# Bank0-13-33.net
KiCad netlist of a schematic drawn in Altium Designer
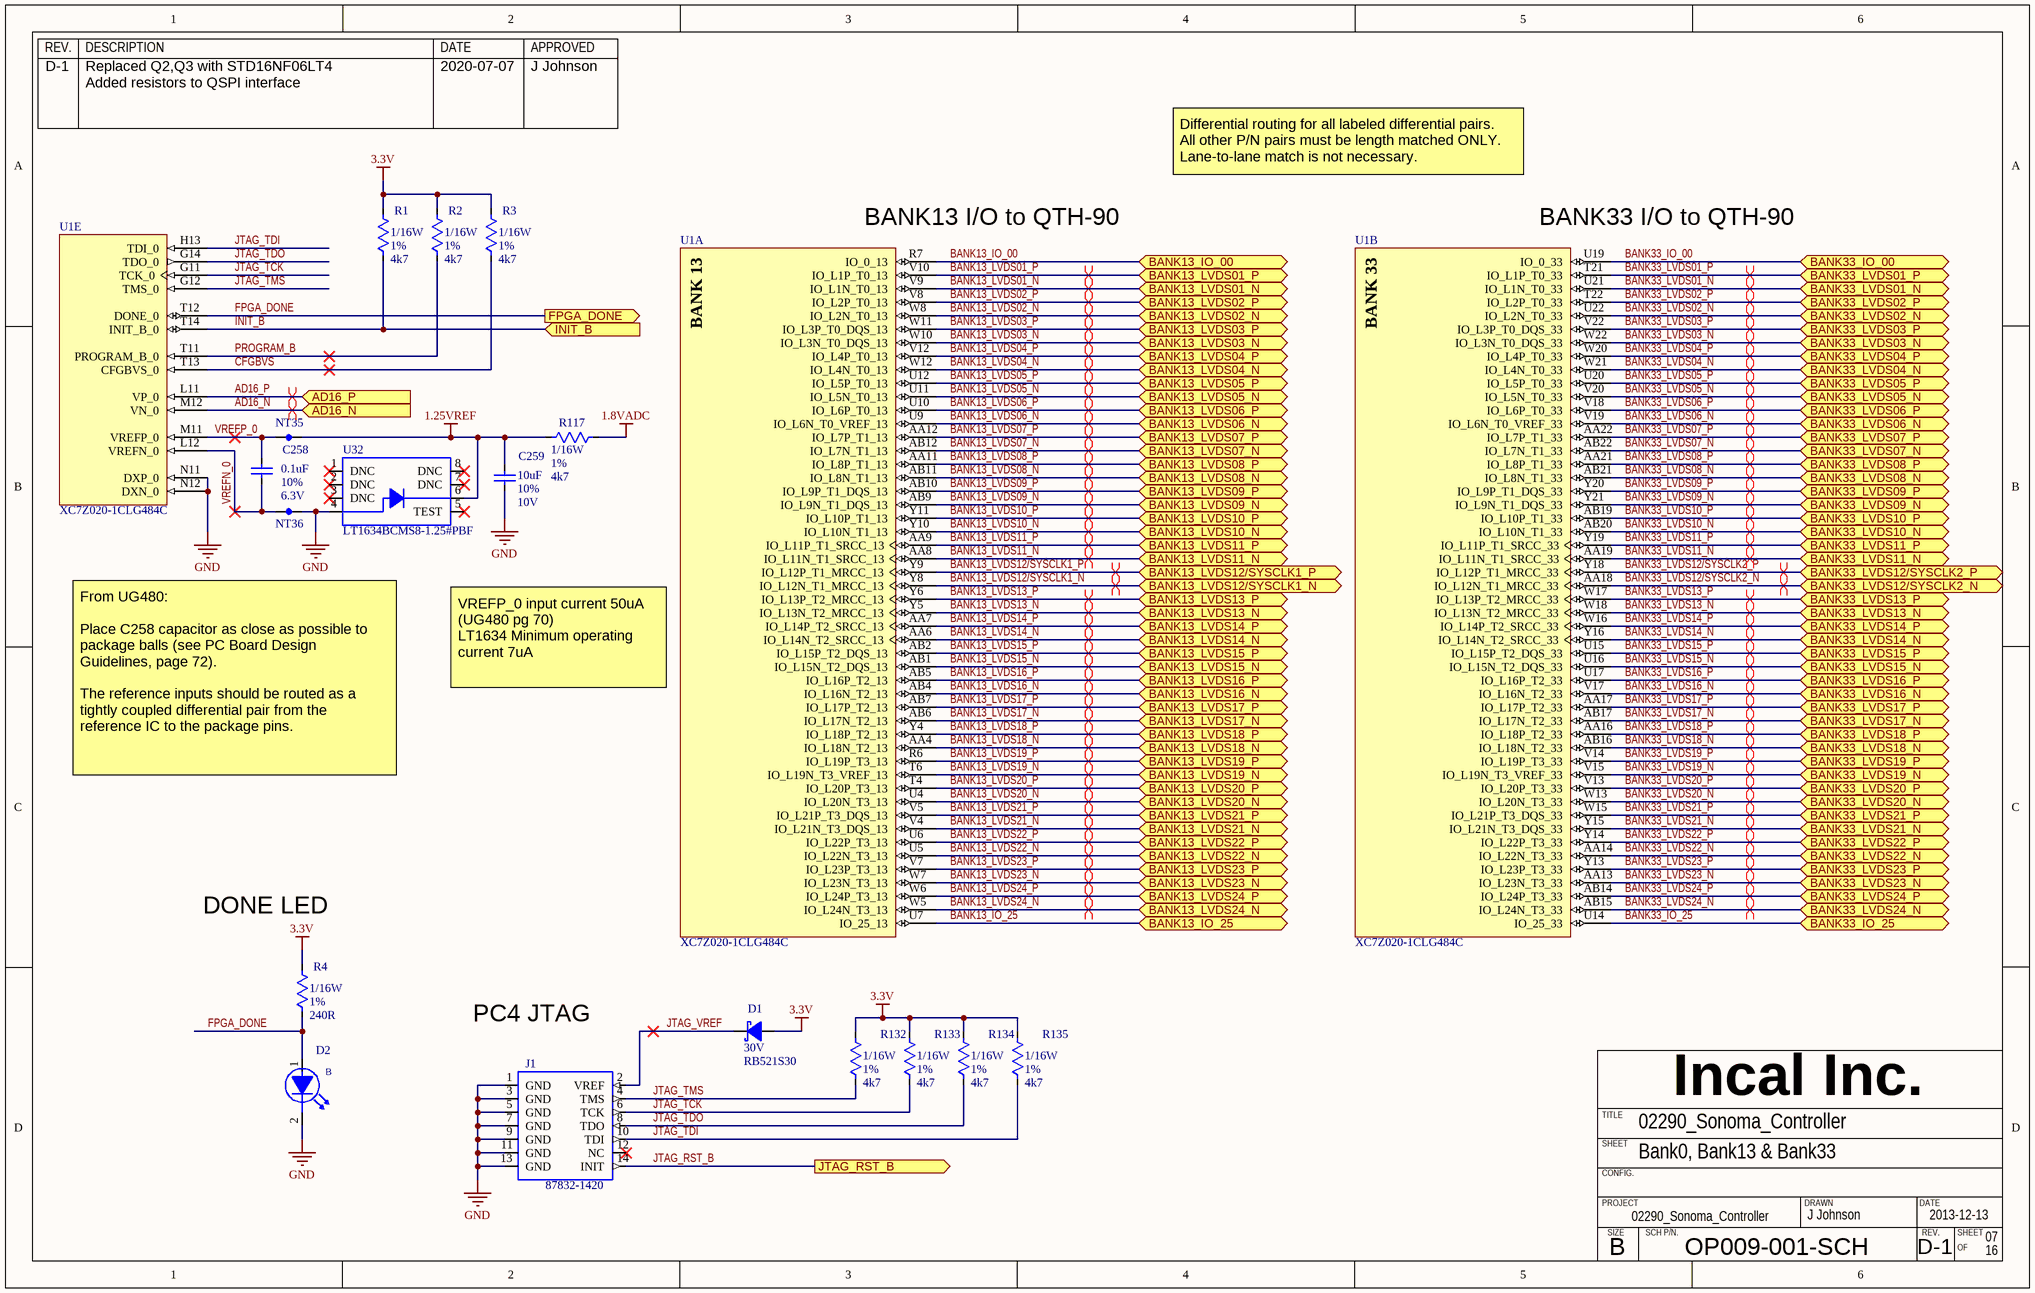
[diagram p0: Bank0-13-33.SchDoc]

(export (version "E")
  (design (tool "Eeschema 10.0.6"))
  (components
    (comp (ref "C258")
      (value "0.1uF")
      (footprint "CAPC0603X33N")
      (description "Capacitor ceramic, X5R, 0.1uF, 6.3V, 10%, -55 to +125 C, EIA0201")
      (fields
        (field (name "TOLERANCE") "10%")
        (field (name "VOLTAGE") "6.3V")
        (field (name "Comment") "CAPACITOR_NP_TYPE1")
      )
      (libsource (lib "parts") (part "CAPACITOR_NP_TYPE1"))
    )
    (comp (ref "C259")
      (value "10uF")
      (footprint "CAPC1608X38N")
      (description "Capacitor ceramic, X5R, 10uF, 10V, 10%, -55 to +85 C, EIA0603")
      (fields
        (field (name "TOLERANCE") "10%")
        (field (name "VOLTAGE") "10V")
        (field (name "Comment") "CAPACITOR_NP_TYPE1")
      )
      (libsource (lib "parts") (part "CAPACITOR_NP_TYPE1"))
    )
    (comp (ref "D1")
      (value "RB521S30")
      (footprint "SOD15080X70")
      (description "Diode schottky, 30V, 200mA, SOD-523F")
      (fields (field (name "VOLTAGE") "30V") (field (name "Comment") "DIODE_SCHOTTKY_TYPE1"))
      (libsource (lib "parts") (part "DIODE_SCHOTTKY_TYPE1"))
    )
    (comp (ref "D2")
      (value "LED_BLU")
      (footprint "LEDM1608X38N-BLU")
      (description "Led, Blue, 150mcd, SMT, LTST-C191TBKT, -20 to +80 C, 0603")
      (fields (field (name "POWER") "120mW") (field (name "VOLTAGE") "3.2V"))
      (libsource (lib "parts") (part "LED_BLU"))
    )
    (comp (ref "J1")
      (value "XILINX-JTAG-2x7")
      (footprint "87832-1420")
      (description "Connector Header 2mm, 2x7, SMT, Keyed, Shrouded, 0V, 0A, -55 to +105 C")
      (fields
        (field (name "POWER") "Pow")
        (field (name "VOLTAGE") "0V")
        (field (name "MFG PART NUMBER 1") "87832-1420")
      )
      (libsource (lib "parts") (part "XILINX-JTAG-2x7"))
    )
    (comp (ref "NT35")
      (value "NET_TIE_1X1")
      (footprint "NET_TIE_1X1")
      (description "Net Tie 1 to 1")
      (libsource (lib "parts") (part "NET_TIE_1X1"))
    )
    (comp (ref "NT36")
      (value "NET_TIE_1X1")
      (footprint "NET_TIE_1X1")
      (description "Net Tie 1 to 1")
      (libsource (lib "parts") (part "NET_TIE_1X1"))
    )
    (comp (ref "R1")
      (value "4k7")
      (footprint "RESC1005X33N")
      (description "Resistor, 4k7, 1/16W, 1%, -55 to +155 C, EIA0402")
      (fields (field (name "VOLTAGE") "50V") (field (name "POWER") "1/16W") (field (name "TOLERANCE") "1%"))
      (libsource (lib "parts") (part "RESISTOR_TYPE1"))
    )
    (comp (ref "R2")
      (value "4k7")
      (footprint "RESC1005X33N")
      (description "Resistor, 4k7, 1/16W, 1%, -55 to +155 C, EIA0402")
      (fields (field (name "VOLTAGE") "50V") (field (name "POWER") "1/16W") (field (name "TOLERANCE") "1%"))
      (libsource (lib "parts") (part "RESISTOR_TYPE1"))
    )
    (comp (ref "R3")
      (value "4k7")
      (footprint "RESC1005X33N")
      (description "Resistor, 4k7, 1/16W, 1%, -55 to +155 C, EIA0402")
      (fields (field (name "VOLTAGE") "50V") (field (name "POWER") "1/16W") (field (name "TOLERANCE") "1%"))
      (libsource (lib "parts") (part "RESISTOR_TYPE1"))
    )
    (comp (ref "R4")
      (value "240R")
      (footprint "RESC1005X33N")
      (description "Resistor, 240R, 1/16W, 1%, -50 to +155 C, EIA0402, EIA(M)1005")
      (fields (field (name "VOLTAGE") "50V") (field (name "POWER") "1/16W") (field (name "TOLERANCE") "1%"))
      (libsource (lib "parts") (part "RESISTOR_TYPE1"))
    )
    (comp (ref "R117")
      (value "4k7")
      (footprint "RESC1005X33N")
      (description "Resistor, 4k7, 1/16W, 1%, -55 to +155 C, EIA0402")
      (fields (field (name "VOLTAGE") "50V") (field (name "POWER") "1/16W") (field (name "TOLERANCE") "1%"))
      (libsource (lib "parts") (part "RESISTOR_TYPE1"))
    )
    (comp (ref "R132")
      (value "4k7")
      (footprint "RESC1005X33N")
      (description "Resistor, 4k7, 1/16W, 1%, -55 to +155 C, EIA0402")
      (fields (field (name "VOLTAGE") "50V") (field (name "POWER") "1/16W") (field (name "TOLERANCE") "1%"))
      (libsource (lib "parts") (part "RESISTOR_TYPE1"))
    )
    (comp (ref "R133")
      (value "4k7")
      (footprint "RESC1005X33N")
      (description "Resistor, 4k7, 1/16W, 1%, -55 to +155 C, EIA0402")
      (fields (field (name "VOLTAGE") "50V") (field (name "POWER") "1/16W") (field (name "TOLERANCE") "1%"))
      (libsource (lib "parts") (part "RESISTOR_TYPE1"))
    )
    (comp (ref "R134")
      (value "4k7")
      (footprint "RESC1005X33N")
      (description "Resistor, 4k7, 1/16W, 1%, -55 to +155 C, EIA0402")
      (fields (field (name "VOLTAGE") "50V") (field (name "POWER") "1/16W") (field (name "TOLERANCE") "1%"))
      (libsource (lib "parts") (part "RESISTOR_TYPE1"))
    )
    (comp (ref "R135")
      (value "4k7")
      (footprint "RESC1005X33N")
      (description "Resistor, 4k7, 1/16W, 1%, -55 to +155 C, EIA0402")
      (fields (field (name "VOLTAGE") "50V") (field (name "POWER") "1/16W") (field (name "TOLERANCE") "1%"))
      (libsource (lib "parts") (part "RESISTOR_TYPE1"))
    )
    (comp (ref "U1")
      (value "XC7Z020-1CLG484C")
      (footprint "CLG484")
      (description "667 MHz Zynq™-7000 AP SoC, 130 PS I/O, 200 FPGA I/O, 484-Ball BGA, Speed Grade 1, Commercial Grade")
      (fields (field (name "GENERIC PART NUMBER") "XC7Z020") (field (name "MANUFACTURER") "Xilinx"))
      (libsource (lib "") (part "XC7Z020-1CLG484C_1"))
    )
    (comp (ref "U32")
      (value "LT1634")
      (footprint "SOP65P490X110-8N")
      (description "Reference Shunt 1.25V, 10ppm, 0.05%")
      (fields
        (field (name "POWER") "Pow")
        (field (name "TOLERANCE") "±0.05%")
        (field (name "MFG PART NUMBER 1") "LT1634BCMS8-1.25#PBF")
      )
      (libsource (lib "parts") (part "LT1634"))
    )
  )
  (nets
    (net (code "1") (name "/AD16_N") (class "Default")
      (node (ref "U1") (pin "M12") (pinfunction "VN_0_M12") (pintype "input"))
    )
    (net (code "2") (name "/AD16_P") (class "Default")
      (node (ref "U1") (pin "L11") (pinfunction "VP_0_L11") (pintype "input"))
    )
    (net (code "3") (name "/BANK13_IO_00") (class "Default")
      (node (ref "U1") (pin "R7") (pinfunction "IO_0_13_R7") (pintype "bidirectional"))
    )
    (net (code "4") (name "/BANK13_IO_25") (class "Default")
      (node (ref "U1") (pin "U7") (pinfunction "IO_25_13_U7") (pintype "bidirectional"))
    )
    (net (code "5") (name "/BANK13_LVDS01_N") (class "Default")
      (node (ref "U1") (pin "V9") (pinfunction "IO_L1N_T0_13_V9") (pintype "bidirectional"))
    )
    (net (code "6") (name "/BANK13_LVDS01_P") (class "Default")
      (node (ref "U1") (pin "V10") (pinfunction "IO_L1P_T0_13_V10") (pintype "bidirectional"))
    )
    (net (code "7") (name "/BANK13_LVDS02_N") (class "Default")
      (node (ref "U1") (pin "W8") (pinfunction "IO_L2N_T0_13_W8") (pintype "bidirectional"))
    )
    (net (code "8") (name "/BANK13_LVDS02_P") (class "Default")
      (node (ref "U1") (pin "V8") (pinfunction "IO_L2P_T0_13_V8") (pintype "bidirectional"))
    )
    (net (code "9") (name "/BANK13_LVDS03_N") (class "Default")
      (node (ref "U1") (pin "W10") (pinfunction "IO_L3N_T0_DQS_13_W10") (pintype "bidirectional"))
    )
    (net (code "10") (name "/BANK13_LVDS03_P") (class "Default")
      (node (ref "U1") (pin "W11") (pinfunction "IO_L3P_T0_DQS_13_W11") (pintype "bidirectional"))
    )
    (net (code "11") (name "/BANK13_LVDS04_N") (class "Default")
      (node (ref "U1") (pin "W12") (pinfunction "IO_L4N_T0_13_W12") (pintype "bidirectional"))
    )
    (net (code "12") (name "/BANK13_LVDS04_P") (class "Default")
      (node (ref "U1") (pin "V12") (pinfunction "IO_L4P_T0_13_V12") (pintype "bidirectional"))
    )
    (net (code "13") (name "/BANK13_LVDS05_N") (class "Default")
      (node (ref "U1") (pin "U11") (pinfunction "IO_L5N_T0_13_U11") (pintype "bidirectional"))
    )
    (net (code "14") (name "/BANK13_LVDS05_P") (class "Default")
      (node (ref "U1") (pin "U12") (pinfunction "IO_L5P_T0_13_U12") (pintype "bidirectional"))
    )
    (net (code "15") (name "/BANK13_LVDS06_N") (class "Default")
      (node (ref "U1") (pin "U9") (pinfunction "IO_L6N_T0_VREF_13_U9") (pintype "bidirectional"))
    )
    (net (code "16") (name "/BANK13_LVDS06_P") (class "Default")
      (node (ref "U1") (pin "U10") (pinfunction "IO_L6P_T0_13_U10") (pintype "bidirectional"))
    )
    (net (code "17") (name "/BANK13_LVDS07_N") (class "Default")
      (node (ref "U1") (pin "AB12") (pinfunction "IO_L7N_T1_13_AB12") (pintype "bidirectional"))
    )
    (net (code "18") (name "/BANK13_LVDS07_P") (class "Default")
      (node (ref "U1") (pin "AA12") (pinfunction "IO_L7P_T1_13_AA12") (pintype "bidirectional"))
    )
    (net (code "19") (name "/BANK13_LVDS08_N") (class "Default")
      (node (ref "U1") (pin "AB11") (pinfunction "IO_L8N_T1_13_AB11") (pintype "bidirectional"))
    )
    (net (code "20") (name "/BANK13_LVDS08_P") (class "Default")
      (node (ref "U1") (pin "AA11") (pinfunction "IO_L8P_T1_13_AA11") (pintype "bidirectional"))
    )
    (net (code "21") (name "/BANK13_LVDS09_N") (class "Default")
      (node (ref "U1") (pin "AB9") (pinfunction "IO_L9N_T1_DQS_13_AB9") (pintype "bidirectional"))
    )
    (net (code "22") (name "/BANK13_LVDS09_P") (class "Default")
      (node (ref "U1") (pin "AB10") (pinfunction "IO_L9P_T1_DQS_13_AB10") (pintype "bidirectional"))
    )
    (net (code "23") (name "/BANK13_LVDS10_N") (class "Default")
      (node (ref "U1") (pin "Y10") (pinfunction "IO_L10N_T1_13_Y10") (pintype "bidirectional"))
    )
    (net (code "24") (name "/BANK13_LVDS10_P") (class "Default")
      (node (ref "U1") (pin "Y11") (pinfunction "IO_L10P_T1_13_Y11") (pintype "bidirectional"))
    )
    (net (code "25") (name "/BANK13_LVDS11_N") (class "Default")
      (node (ref "U1") (pin "AA8") (pinfunction "IO_L11N_T1_SRCC_13_AA8") (pintype "bidirectional"))
    )
    (net (code "26") (name "/BANK13_LVDS11_P") (class "Default")
      (node (ref "U1") (pin "AA9") (pinfunction "IO_L11P_T1_SRCC_13_AA9") (pintype "bidirectional"))
    )
    (net (code "27") (name "/BANK13_LVDS12{slash}SYSCLK1_N") (class "Default")
      (node (ref "U1") (pin "Y8") (pinfunction "IO_L12N_T1_MRCC_13_Y8") (pintype "bidirectional"))
    )
    (net (code "28") (name "/BANK13_LVDS12{slash}SYSCLK1_P") (class "Default")
      (node (ref "U1") (pin "Y9") (pinfunction "IO_L12P_T1_MRCC_13_Y9") (pintype "bidirectional"))
    )
    (net (code "29") (name "/BANK13_LVDS13_N") (class "Default")
      (node (ref "U1") (pin "Y5") (pinfunction "IO_L13N_T2_MRCC_13_Y5") (pintype "bidirectional"))
    )
    (net (code "30") (name "/BANK13_LVDS13_P") (class "Default")
      (node (ref "U1") (pin "Y6") (pinfunction "IO_L13P_T2_MRCC_13_Y6") (pintype "bidirectional"))
    )
    (net (code "31") (name "/BANK13_LVDS14_N") (class "Default")
      (node (ref "U1") (pin "AA6") (pinfunction "IO_L14N_T2_SRCC_13_AA6") (pintype "bidirectional"))
    )
    (net (code "32") (name "/BANK13_LVDS14_P") (class "Default")
      (node (ref "U1") (pin "AA7") (pinfunction "IO_L14P_T2_SRCC_13_AA7") (pintype "bidirectional"))
    )
    (net (code "33") (name "/BANK13_LVDS15_N") (class "Default")
      (node (ref "U1") (pin "AB1") (pinfunction "IO_L15N_T2_DQS_13_AB1") (pintype "bidirectional"))
    )
    (net (code "34") (name "/BANK13_LVDS15_P") (class "Default")
      (node (ref "U1") (pin "AB2") (pinfunction "IO_L15P_T2_DQS_13_AB2") (pintype "bidirectional"))
    )
    (net (code "35") (name "/BANK13_LVDS16_N") (class "Default")
      (node (ref "U1") (pin "AB4") (pinfunction "IO_L16N_T2_13_AB4") (pintype "bidirectional"))
    )
    (net (code "36") (name "/BANK13_LVDS16_P") (class "Default")
      (node (ref "U1") (pin "AB5") (pinfunction "IO_L16P_T2_13_AB5") (pintype "bidirectional"))
    )
    (net (code "37") (name "/BANK13_LVDS17_N") (class "Default")
      (node (ref "U1") (pin "AB6") (pinfunction "IO_L17N_T2_13_AB6") (pintype "bidirectional"))
    )
    (net (code "38") (name "/BANK13_LVDS17_P") (class "Default")
      (node (ref "U1") (pin "AB7") (pinfunction "IO_L17P_T2_13_AB7") (pintype "bidirectional"))
    )
    (net (code "39") (name "/BANK13_LVDS18_N") (class "Default")
      (node (ref "U1") (pin "AA4") (pinfunction "IO_L18N_T2_13_AA4") (pintype "bidirectional"))
    )
    (net (code "40") (name "/BANK13_LVDS18_P") (class "Default")
      (node (ref "U1") (pin "Y4") (pinfunction "IO_L18P_T2_13_Y4") (pintype "bidirectional"))
    )
    (net (code "41") (name "/BANK13_LVDS19_N") (class "Default")
      (node (ref "U1") (pin "T6") (pinfunction "IO_L19N_T3_VREF_13_T6") (pintype "bidirectional"))
    )
    (net (code "42") (name "/BANK13_LVDS19_P") (class "Default")
      (node (ref "U1") (pin "R6") (pinfunction "IO_L19P_T3_13_R6") (pintype "bidirectional"))
    )
    (net (code "43") (name "/BANK13_LVDS20_N") (class "Default")
      (node (ref "U1") (pin "U4") (pinfunction "IO_L20N_T3_13_U4") (pintype "bidirectional"))
    )
    (net (code "44") (name "/BANK13_LVDS20_P") (class "Default")
      (node (ref "U1") (pin "T4") (pinfunction "IO_L20P_T3_13_T4") (pintype "bidirectional"))
    )
    (net (code "45") (name "/BANK13_LVDS21_N") (class "Default")
      (node (ref "U1") (pin "V4") (pinfunction "IO_L21N_T3_DQS_13_V4") (pintype "bidirectional"))
    )
    (net (code "46") (name "/BANK13_LVDS21_P") (class "Default")
      (node (ref "U1") (pin "V5") (pinfunction "IO_L21P_T3_DQS_13_V5") (pintype "bidirectional"))
    )
    (net (code "47") (name "/BANK13_LVDS22_N") (class "Default")
      (node (ref "U1") (pin "U5") (pinfunction "IO_L22N_T3_13_U5") (pintype "bidirectional"))
    )
    (net (code "48") (name "/BANK13_LVDS22_P") (class "Default")
      (node (ref "U1") (pin "U6") (pinfunction "IO_L22P_T3_13_U6") (pintype "bidirectional"))
    )
    (net (code "49") (name "/BANK13_LVDS23_N") (class "Default")
      (node (ref "U1") (pin "W7") (pinfunction "IO_L23N_T3_13_W7") (pintype "bidirectional"))
    )
    (net (code "50") (name "/BANK13_LVDS23_P") (class "Default")
      (node (ref "U1") (pin "V7") (pinfunction "IO_L23P_T3_13_V7") (pintype "bidirectional"))
    )
    (net (code "51") (name "/BANK13_LVDS24_N") (class "Default")
      (node (ref "U1") (pin "W5") (pinfunction "IO_L24N_T3_13_W5") (pintype "bidirectional"))
    )
    (net (code "52") (name "/BANK13_LVDS24_P") (class "Default")
      (node (ref "U1") (pin "W6") (pinfunction "IO_L24P_T3_13_W6") (pintype "bidirectional"))
    )
    (net (code "53") (name "/BANK33_IO_00") (class "Default")
      (node (ref "U1") (pin "U19") (pinfunction "IO_0_33_U19") (pintype "bidirectional"))
    )
    (net (code "54") (name "/BANK33_IO_25") (class "Default")
      (node (ref "U1") (pin "U14") (pinfunction "IO_25_33_U14") (pintype "bidirectional"))
    )
    (net (code "55") (name "/BANK33_LVDS01_N") (class "Default")
      (node (ref "U1") (pin "U21") (pinfunction "IO_L1N_T0_33_U21") (pintype "bidirectional"))
    )
    (net (code "56") (name "/BANK33_LVDS01_P") (class "Default")
      (node (ref "U1") (pin "T21") (pinfunction "IO_L1P_T0_33_T21") (pintype "bidirectional"))
    )
    (net (code "57") (name "/BANK33_LVDS02_N") (class "Default")
      (node (ref "U1") (pin "U22") (pinfunction "IO_L2N_T0_33_U22") (pintype "bidirectional"))
    )
    (net (code "58") (name "/BANK33_LVDS02_P") (class "Default")
      (node (ref "U1") (pin "T22") (pinfunction "IO_L2P_T0_33_T22") (pintype "bidirectional"))
    )
    (net (code "59") (name "/BANK33_LVDS03_N") (class "Default")
      (node (ref "U1") (pin "W22") (pinfunction "IO_L3N_T0_DQS_33_W22") (pintype "bidirectional"))
    )
    (net (code "60") (name "/BANK33_LVDS03_P") (class "Default")
      (node (ref "U1") (pin "V22") (pinfunction "IO_L3P_T0_DQS_33_V22") (pintype "bidirectional"))
    )
    (net (code "61") (name "/BANK33_LVDS04_N") (class "Default")
      (node (ref "U1") (pin "W21") (pinfunction "IO_L4N_T0_33_W21") (pintype "bidirectional"))
    )
    (net (code "62") (name "/BANK33_LVDS04_P") (class "Default")
      (node (ref "U1") (pin "W20") (pinfunction "IO_L4P_T0_33_W20") (pintype "bidirectional"))
    )
    (net (code "63") (name "/BANK33_LVDS05_N") (class "Default")
      (node (ref "U1") (pin "V20") (pinfunction "IO_L5N_T0_33_V20") (pintype "bidirectional"))
    )
    (net (code "64") (name "/BANK33_LVDS05_P") (class "Default")
      (node (ref "U1") (pin "U20") (pinfunction "IO_L5P_T0_33_U20") (pintype "bidirectional"))
    )
    (net (code "65") (name "/BANK33_LVDS06_N") (class "Default")
      (node (ref "U1") (pin "V19") (pinfunction "IO_L6N_T0_VREF_33_V19") (pintype "bidirectional"))
    )
    (net (code "66") (name "/BANK33_LVDS06_P") (class "Default")
      (node (ref "U1") (pin "V18") (pinfunction "IO_L6P_T0_33_V18") (pintype "bidirectional"))
    )
    (net (code "67") (name "/BANK33_LVDS07_N") (class "Default")
      (node (ref "U1") (pin "AB22") (pinfunction "IO_L7N_T1_33_AB22") (pintype "bidirectional"))
    )
    (net (code "68") (name "/BANK33_LVDS07_P") (class "Default")
      (node (ref "U1") (pin "AA22") (pinfunction "IO_L7P_T1_33_AA22") (pintype "bidirectional"))
    )
    (net (code "69") (name "/BANK33_LVDS08_N") (class "Default")
      (node (ref "U1") (pin "AB21") (pinfunction "IO_L8N_T1_33_AB21") (pintype "bidirectional"))
    )
    (net (code "70") (name "/BANK33_LVDS08_P") (class "Default")
      (node (ref "U1") (pin "AA21") (pinfunction "IO_L8P_T1_33_AA21") (pintype "bidirectional"))
    )
    (net (code "71") (name "/BANK33_LVDS09_N") (class "Default")
      (node (ref "U1") (pin "Y21") (pinfunction "IO_L9N_T1_DQS_33_Y21") (pintype "bidirectional"))
    )
    (net (code "72") (name "/BANK33_LVDS09_P") (class "Default")
      (node (ref "U1") (pin "Y20") (pinfunction "IO_L9P_T1_DQS_33_Y20") (pintype "bidirectional"))
    )
    (net (code "73") (name "/BANK33_LVDS10_N") (class "Default")
      (node (ref "U1") (pin "AB20") (pinfunction "IO_L10N_T1_33_AB20") (pintype "bidirectional"))
    )
    (net (code "74") (name "/BANK33_LVDS10_P") (class "Default")
      (node (ref "U1") (pin "AB19") (pinfunction "IO_L10P_T1_33_AB19") (pintype "bidirectional"))
    )
    (net (code "75") (name "/BANK33_LVDS11_N") (class "Default")
      (node (ref "U1") (pin "AA19") (pinfunction "IO_L11N_T1_SRCC_33_AA19") (pintype "bidirectional"))
    )
    (net (code "76") (name "/BANK33_LVDS11_P") (class "Default")
      (node (ref "U1") (pin "Y19") (pinfunction "IO_L11P_T1_SRCC_33_Y19") (pintype "bidirectional"))
    )
    (net (code "77") (name "/BANK33_LVDS12{slash}SYSCLK2_N") (class "Default")
      (node (ref "U1") (pin "AA18") (pinfunction "IO_L12N_T1_MRCC_33_AA18") (pintype "bidirectional"))
    )
    (net (code "78") (name "/BANK33_LVDS12{slash}SYSCLK2_P") (class "Default")
      (node (ref "U1") (pin "Y18") (pinfunction "IO_L12P_T1_MRCC_33_Y18") (pintype "bidirectional"))
    )
    (net (code "79") (name "/BANK33_LVDS13_N") (class "Default")
      (node (ref "U1") (pin "W18") (pinfunction "IO_L13N_T2_MRCC_33_W18") (pintype "bidirectional"))
    )
    (net (code "80") (name "/BANK33_LVDS13_P") (class "Default")
      (node (ref "U1") (pin "W17") (pinfunction "IO_L13P_T2_MRCC_33_W17") (pintype "bidirectional"))
    )
    (net (code "81") (name "/BANK33_LVDS14_N") (class "Default")
      (node (ref "U1") (pin "Y16") (pinfunction "IO_L14N_T2_SRCC_33_Y16") (pintype "bidirectional"))
    )
    (net (code "82") (name "/BANK33_LVDS14_P") (class "Default")
      (node (ref "U1") (pin "W16") (pinfunction "IO_L14P_T2_SRCC_33_W16") (pintype "bidirectional"))
    )
    (net (code "83") (name "/BANK33_LVDS15_N") (class "Default")
      (node (ref "U1") (pin "U16") (pinfunction "IO_L15N_T2_DQS_33_U16") (pintype "bidirectional"))
    )
    (net (code "84") (name "/BANK33_LVDS15_P") (class "Default")
      (node (ref "U1") (pin "U15") (pinfunction "IO_L15P_T2_DQS_33_U15") (pintype "bidirectional"))
    )
    (net (code "85") (name "/BANK33_LVDS16_N") (class "Default")
      (node (ref "U1") (pin "V17") (pinfunction "IO_L16N_T2_33_V17") (pintype "bidirectional"))
    )
    (net (code "86") (name "/BANK33_LVDS16_P") (class "Default")
      (node (ref "U1") (pin "U17") (pinfunction "IO_L16P_T2_33_U17") (pintype "bidirectional"))
    )
    (net (code "87") (name "/BANK33_LVDS17_N") (class "Default")
      (node (ref "U1") (pin "AB17") (pinfunction "IO_L17N_T2_33_AB17") (pintype "bidirectional"))
    )
    (net (code "88") (name "/BANK33_LVDS17_P") (class "Default")
      (node (ref "U1") (pin "AA17") (pinfunction "IO_L17P_T2_33_AA17") (pintype "bidirectional"))
    )
    (net (code "89") (name "/BANK33_LVDS18_N") (class "Default")
      (node (ref "U1") (pin "AB16") (pinfunction "IO_L18N_T2_33_AB16") (pintype "bidirectional"))
    )
    (net (code "90") (name "/BANK33_LVDS18_P") (class "Default")
      (node (ref "U1") (pin "AA16") (pinfunction "IO_L18P_T2_33_AA16") (pintype "bidirectional"))
    )
    (net (code "91") (name "/BANK33_LVDS19_N") (class "Default")
      (node (ref "U1") (pin "V15") (pinfunction "IO_L19N_T3_VREF_33_V15") (pintype "bidirectional"))
    )
    (net (code "92") (name "/BANK33_LVDS19_P") (class "Default")
      (node (ref "U1") (pin "V14") (pinfunction "IO_L19P_T3_33_V14") (pintype "bidirectional"))
    )
    (net (code "93") (name "/BANK33_LVDS20_N") (class "Default")
      (node (ref "U1") (pin "W13") (pinfunction "IO_L20N_T3_33_W13") (pintype "bidirectional"))
    )
    (net (code "94") (name "/BANK33_LVDS20_P") (class "Default")
      (node (ref "U1") (pin "V13") (pinfunction "IO_L20P_T3_33_V13") (pintype "bidirectional"))
    )
    (net (code "95") (name "/BANK33_LVDS21_N") (class "Default")
      (node (ref "U1") (pin "Y15") (pinfunction "IO_L21N_T3_DQS_33_Y15") (pintype "bidirectional"))
    )
    (net (code "96") (name "/BANK33_LVDS21_P") (class "Default")
      (node (ref "U1") (pin "W15") (pinfunction "IO_L21P_T3_DQS_33_W15") (pintype "bidirectional"))
    )
    (net (code "97") (name "/BANK33_LVDS22_N") (class "Default")
      (node (ref "U1") (pin "AA14") (pinfunction "IO_L22N_T3_33_AA14") (pintype "bidirectional"))
    )
    (net (code "98") (name "/BANK33_LVDS22_P") (class "Default")
      (node (ref "U1") (pin "Y14") (pinfunction "IO_L22P_T3_33_Y14") (pintype "bidirectional"))
    )
    (net (code "99") (name "/BANK33_LVDS23_N") (class "Default")
      (node (ref "U1") (pin "AA13") (pinfunction "IO_L23N_T3_33_AA13") (pintype "bidirectional"))
    )
    (net (code "100") (name "/BANK33_LVDS23_P") (class "Default")
      (node (ref "U1") (pin "Y13") (pinfunction "IO_L23P_T3_33_Y13") (pintype "bidirectional"))
    )
    (net (code "101") (name "/BANK33_LVDS24_N") (class "Default")
      (node (ref "U1") (pin "AB15") (pinfunction "IO_L24N_T3_33_AB15") (pintype "bidirectional"))
    )
    (net (code "102") (name "/BANK33_LVDS24_P") (class "Default")
      (node (ref "U1") (pin "AB14") (pinfunction "IO_L24P_T3_33_AB14") (pintype "bidirectional"))
    )
    (net (code "103") (name "/CFGBVS") (class "Default")
      (node (ref "R3") (pin "1") (pinfunction "1_1") (pintype "passive"))
      (node (ref "U1") (pin "T13") (pinfunction "CFGBVS_0_T13") (pintype "input"))
    )
    (net (code "104") (name "/FPGA_DONE") (class "Default")
      (node (ref "D2") (pin "1") (pinfunction "A_1") (pintype "passive"))
      (node (ref "R4") (pin "1") (pinfunction "1_1") (pintype "passive"))
      (node (ref "U1") (pin "T12") (pinfunction "DONE_0_T12") (pintype "bidirectional"))
    )
    (net (code "105") (name "/INIT_B") (class "Default")
      (node (ref "R1") (pin "1") (pinfunction "1_1") (pintype "passive"))
      (node (ref "U1") (pin "T14") (pinfunction "INIT_B_0_T14") (pintype "bidirectional"))
    )
    (net (code "106") (name "/JTAG_RST_B") (class "Default")
      (node (ref "J1") (pin "14") (pinfunction "INIT_14") (pintype "output"))
    )
    (net (code "107") (name "/JTAG_TCK") (class "Default")
      (node (ref "J1") (pin "6") (pinfunction "TCK_6") (pintype "output"))
      (node (ref "R133") (pin "1") (pinfunction "1_1") (pintype "passive"))
      (node (ref "U1") (pin "G11") (pinfunction "TCK_0_G11") (pintype "input"))
    )
    (net (code "108") (name "/JTAG_TDI") (class "Default")
      (node (ref "J1") (pin "10") (pinfunction "TDI_10") (pintype "output"))
      (node (ref "R135") (pin "1") (pinfunction "1_1") (pintype "passive"))
      (node (ref "U1") (pin "H13") (pinfunction "TDI_0_H13") (pintype "input"))
    )
    (net (code "109") (name "/JTAG_TDO") (class "Default")
      (node (ref "J1") (pin "8") (pinfunction "TDO_8") (pintype "input"))
      (node (ref "R134") (pin "1") (pinfunction "1_1") (pintype "passive"))
      (node (ref "U1") (pin "G14") (pinfunction "TDO_0_G14") (pintype "output"))
    )
    (net (code "110") (name "/JTAG_TMS") (class "Default")
      (node (ref "J1") (pin "4") (pinfunction "TMS_4") (pintype "output"))
      (node (ref "R132") (pin "1") (pinfunction "1_1") (pintype "passive"))
      (node (ref "U1") (pin "G12") (pinfunction "TMS_0_G12") (pintype "input"))
    )
    (net (code "111") (name "/JTAG_VREF") (class "Default")
      (node (ref "D1") (pin "2") (pinfunction "K_2") (pintype "passive"))
      (node (ref "J1") (pin "2") (pinfunction "VREF_2") (pintype "input"))
    )
    (net (code "112") (name "/PROGRAM_B") (class "Default")
      (node (ref "R2") (pin "1") (pinfunction "1_1") (pintype "passive"))
      (node (ref "U1") (pin "T11") (pinfunction "PROGRAM_B_0_T11") (pintype "input"))
    )
    (net (code "113") (name "/VREFN_0") (class "Default")
      (node (ref "C258") (pin "2") (pinfunction "2_2") (pintype "passive"))
      (node (ref "NT36") (pin "1") (pinfunction "1_1") (pintype "passive"))
      (node (ref "U1") (pin "L12") (pinfunction "VREFN_0_L12") (pintype "input"))
    )
    (net (code "114") (name "/VREFP_0") (class "Default")
      (node (ref "C258") (pin "1") (pinfunction "1_1") (pintype "passive"))
      (node (ref "NT35") (pin "1") (pinfunction "1_1") (pintype "passive"))
      (node (ref "U1") (pin "M11") (pinfunction "VREFP_0_M11") (pintype "input"))
    )
    (net (code "115") (name "1.8VADC") (class "Default")
      (node (ref "R117") (pin "2") (pinfunction "2_2") (pintype "passive"))
    )
    (net (code "116") (name "1.25VREF") (class "Default")
      (node (ref "C259") (pin "1") (pinfunction "1_1") (pintype "passive"))
      (node (ref "NT35") (pin "2") (pinfunction "2_2") (pintype "passive"))
      (node (ref "R117") (pin "1") (pinfunction "1_1") (pintype "passive"))
      (node (ref "U32") (pin "6") (pinfunction "VOUT_6") (pintype "passive"))
    )
    (net (code "117") (name "3.3V") (class "Default")
      (node (ref "D1") (pin "1") (pinfunction "A_1") (pintype "passive"))
      (node (ref "R1") (pin "2") (pinfunction "2_2") (pintype "passive"))
      (node (ref "R132") (pin "2") (pinfunction "2_2") (pintype "passive"))
      (node (ref "R133") (pin "2") (pinfunction "2_2") (pintype "passive"))
      (node (ref "R134") (pin "2") (pinfunction "2_2") (pintype "passive"))
      (node (ref "R135") (pin "2") (pinfunction "2_2") (pintype "passive"))
      (node (ref "R2") (pin "2") (pinfunction "2_2") (pintype "passive"))
      (node (ref "R3") (pin "2") (pinfunction "2_2") (pintype "passive"))
      (node (ref "R4") (pin "2") (pinfunction "2_2") (pintype "passive"))
    )
    (net (code "118") (name "GND") (class "Default")
      (node (ref "C259") (pin "2") (pinfunction "2_2") (pintype "passive"))
      (node (ref "D2") (pin "2") (pinfunction "K_2") (pintype "passive"))
      (node (ref "J1") (pin "1") (pinfunction "GND_1") (pintype "passive"))
      (node (ref "J1") (pin "11") (pinfunction "GND_11") (pintype "passive"))
      (node (ref "J1") (pin "13") (pinfunction "GND_13") (pintype "passive"))
      (node (ref "J1") (pin "3") (pinfunction "GND_3") (pintype "passive"))
      (node (ref "J1") (pin "5") (pinfunction "GND_5") (pintype "passive"))
      (node (ref "J1") (pin "7") (pinfunction "GND_7") (pintype "passive"))
      (node (ref "J1") (pin "9") (pinfunction "GND_9") (pintype "passive"))
      (node (ref "NT36") (pin "2") (pinfunction "2_2") (pintype "passive"))
      (node (ref "U1") (pin "N11") (pinfunction "DXP_0_N11") (pintype "input"))
      (node (ref "U1") (pin "N12") (pinfunction "DXN_0_N12") (pintype "input"))
      (node (ref "U32") (pin "4") (pinfunction "GND_4") (pintype "passive"))
    )
    (net (code "119") (name "unconnected-(J1-NC-Pad12)") (class "Default")
      (node (ref "J1") (pin "12") (pinfunction "NC_12") (pintype "passive+no_connect"))
    )
    (net (code "120") (name "unconnected-(U32-DNC-Pad1)") (class "Default")
      (node (ref "U32") (pin "1") (pinfunction "DNC_1") (pintype "passive+no_connect"))
    )
    (net (code "121") (name "unconnected-(U32-DNC-Pad2)") (class "Default")
      (node (ref "U32") (pin "2") (pinfunction "DNC_2") (pintype "passive+no_connect"))
    )
    (net (code "122") (name "unconnected-(U32-DNC-Pad3)") (class "Default")
      (node (ref "U32") (pin "3") (pinfunction "DNC_3") (pintype "passive+no_connect"))
    )
    (net (code "123") (name "unconnected-(U32-DNC-Pad7)") (class "Default")
      (node (ref "U32") (pin "7") (pinfunction "DNC_7") (pintype "passive+no_connect"))
    )
    (net (code "124") (name "unconnected-(U32-DNC-Pad8)") (class "Default")
      (node (ref "U32") (pin "8") (pinfunction "DNC_8") (pintype "passive+no_connect"))
    )
    (net (code "125") (name "unconnected-(U32-TEST-Pad5)") (class "Default")
      (node (ref "U32") (pin "5") (pinfunction "TEST_5") (pintype "passive+no_connect"))
    )
  )
)
